# NixieDriver.net
KiCad netlist of a schematic drawn in Altium Designer
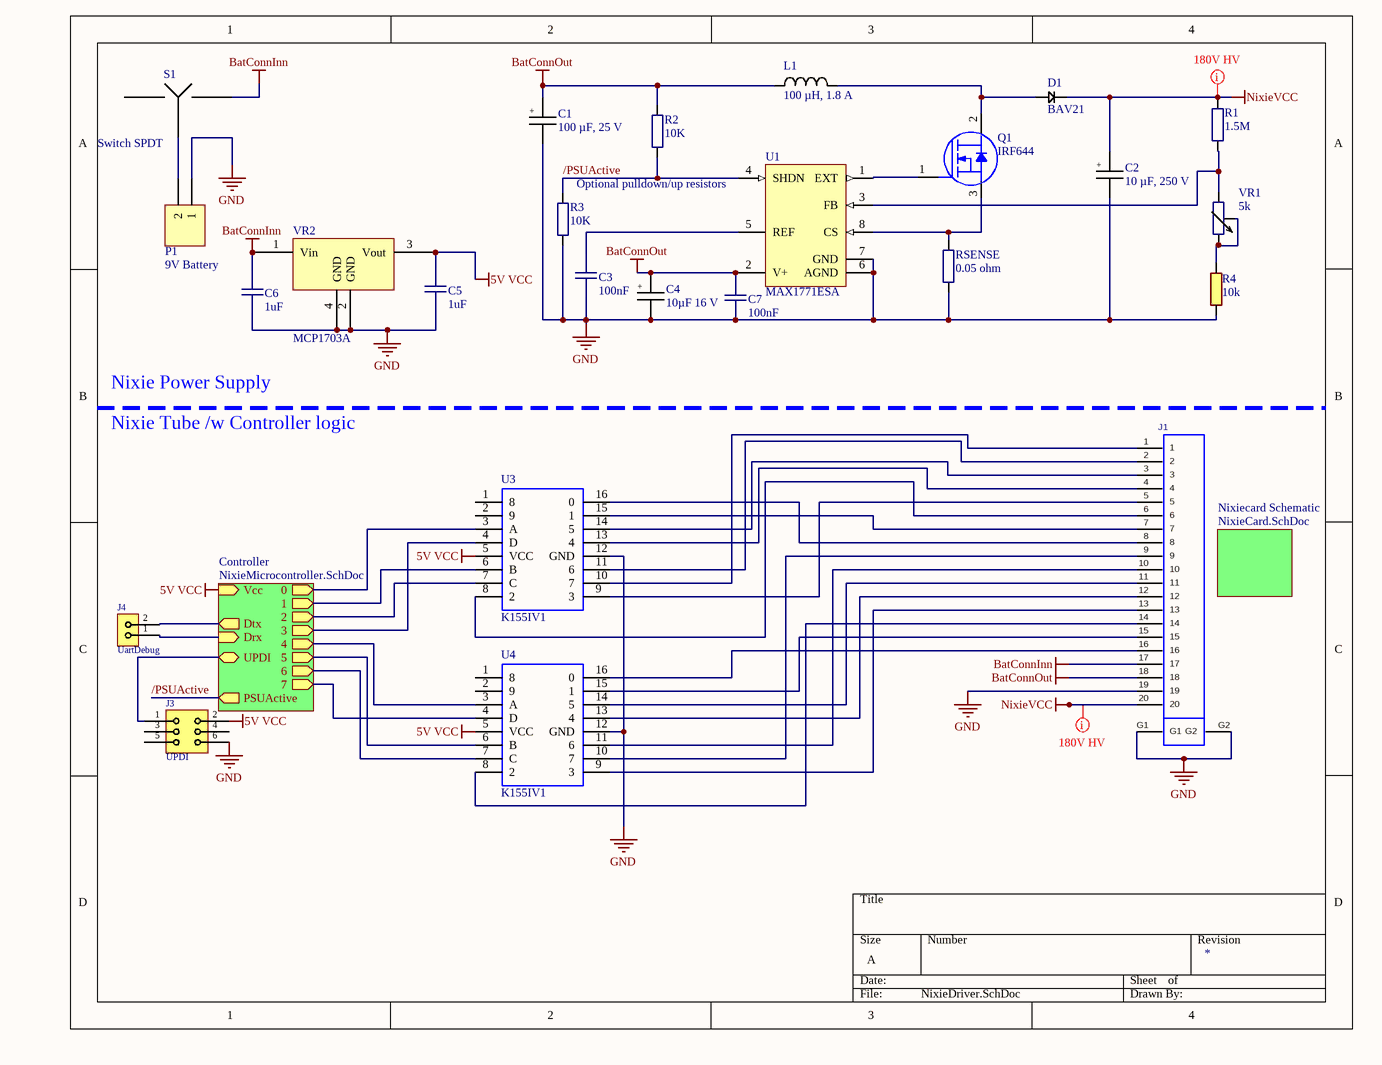
[diagram p0: NixieDriver.SchDoc, right]

(export (version "E")
  (design (tool "Eeschema 10.0.6"))
  (components
    (comp (ref "C1")
      (value "100 µF, 25 V")
      (footprint "CAPAE9583X65M")
      (libsource (lib "Schlib1") (part "EEEFK1E101P"))
    )
    (comp (ref "C2")
      (value "10 µF, 250 V")
      (footprint "CAPAE112103X170M")
      (libsource (lib "Schlib1") (part "EEVEB2E100Q"))
    )
    (comp (ref "C3")
      (value "100nF")
      (footprint "CAPC0805(2012)100_N")
      (description "X7R 50V")
      (libsource (lib "OVLib_64") (part "CAP"))
    )
    (comp (ref "C4")
      (value "10µF 16 V")
      (footprint "CAPAE5542X55M")
      (libsource (lib "Schlib1") (part "EEEFC1C100R"))
    )
    (comp (ref "C5")
      (value "1uF")
      (footprint "CAPC0805(2012)100_N")
      (description "X7R 50V 10%")
      (libsource (lib "OVLib_64") (part "CAP"))
    )
    (comp (ref "C6")
      (value "1uF")
      (footprint "CAPC0805(2012)100_N")
      (description "X7R 50V 10%")
      (libsource (lib "OVLib_64") (part "CAP"))
    )
    (comp (ref "C7")
      (value "100nF")
      (footprint "CAPC0805(2012)100_N")
      (description "X7R 50V")
      (libsource (lib "OVLib_64") (part "CAP"))
    )
    (comp (ref "D1") (value "BAV21") (footprint "DO-41") (libsource (lib "OVLib_64") (part "Diode")))
    (comp (ref "J1")
      (value "ZF1-20-01-XX-WT")
      (footprint "ZF1-20-01-XX-WT")
      (description "ZERO INSERTION FORCE 1mm ASSEMBLY, BOTTOM CONTACT.")
      (libsource (lib "ZF1-20-01-XX-WT") (part "ZF1-20-01-XX-WT"))
    )
    (comp (ref "J3")
      (value "UPDI")
      (footprint "HDRV6W64P254_2X3_762X508X900B")
      (libsource (lib "OVLib_64") (part "Header2x3"))
    )
    (comp (ref "J4")
      (value "UartDebug")
      (footprint "HDRV2W64P254_1X2_508X254X900B")
      (libsource (lib "OVLib_64") (part "Header1x2"))
    )
    (comp (ref "L1")
      (value "100 µH, 1.8 A")
      (footprint "B82479A1")
      (libsource (lib "Schlib1") (part "B82479A1104M"))
    )
    (comp (ref "P1")
      (value "9V Battery")
      (footprint "HDR1X2")
      (description "Header, 2-Pin")
      (fields (field (name "PUBLISHER") "Altium Limited"))
      (libsource (lib "Miscellaneous Connectors") (part "Header 2"))
    )
    (comp (ref "Q1")
      (value "IRF644")
      (footprint "TO-220-3P")
      (description "Power MOSFET")
      (libsource (lib "OVLib_64") (part "MOSFET_N_GDS"))
    )
    (comp (ref "R1") (value "1.5M") (footprint "RC2512") (libsource (lib "Schlib1") (part "Resistor")))
    (comp (ref "R2") (value "10K") (footprint "R0805") (libsource (lib "Schlib1") (part "Resistor")))
    (comp (ref "R3") (value "10K") (footprint "R0805") (libsource (lib "Schlib1") (part "Resistor")))
    (comp (ref "R4")
      (value "10k")
      (footprint "RESC0805(2012)_N")
      (description "0.1W 1% Thick film resistor")
      (libsource (lib "OVLib_64") (part "Resistor2"))
    )
    (comp (ref "RSENSE")
      (value "0.05 ohm")
      (footprint "LR2010")
      (libsource (lib "Schlib1") (part "Resistor"))
    )
    (comp (ref "S1") (value "Switch SPDT") (footprint "3TH") (libsource (lib "Schlib1") (part "Switch SPDT")))
    (comp (ref "U1")
      (value "MAX1771ESA")
      (footprint "S8-5_L")
      (fields (field (name "MANUFACTURER") "Maxim"))
      (libsource (lib "Altium Content Vault") (part "MAXM-MAX1771-8"))
    )
    (comp (ref "U3")
      (value "K155IV1")
      (footprint "CircuitWorks-DIP16")
      (libsource (lib "OVLib_64") (part "SN74141"))
    )
    (comp (ref "U4")
      (value "K155IV1")
      (footprint "CircuitWorks-DIP16")
      (libsource (lib "OVLib_64") (part "SN74141"))
    )
    (comp (ref "VR1")
      (value "5k")
      (footprint "PVG3A trimpot")
      (libsource (lib "Schlib1") (part "PVG3A502C01R00"))
    )
    (comp (ref "VR2")
      (value "MCP1703A")
      (footprint "SOT230P700X180-4N")
      (libsource (lib "Schlib1") (part "MCP1703A"))
    )
  )
  (nets
    (net (code "1") (name "/0") (class "Default")
      (node (ref "U3") (pin "3") (pinfunction "A_3") (pintype "passive"))
    )
    (net (code "2") (name "/1") (class "Default")
      (node (ref "U3") (pin "6") (pinfunction "B_6") (pintype "passive"))
    )
    (net (code "3") (name "/2") (class "Default")
      (node (ref "U3") (pin "7") (pinfunction "C_7") (pintype "passive"))
    )
    (net (code "4") (name "/3") (class "Default")
      (node (ref "U3") (pin "4") (pinfunction "D_4") (pintype "passive"))
    )
    (net (code "5") (name "/4") (class "Default")
      (node (ref "U4") (pin "3") (pinfunction "A_3") (pintype "passive"))
    )
    (net (code "6") (name "/5") (class "Default")
      (node (ref "U4") (pin "6") (pinfunction "B_6") (pintype "passive"))
    )
    (net (code "7") (name "/6") (class "Default")
      (node (ref "U4") (pin "7") (pinfunction "C_7") (pintype "passive"))
    )
    (net (code "8") (name "/7") (class "Default")
      (node (ref "U4") (pin "4") (pinfunction "D_4") (pintype "passive"))
    )
    (net (code "9") (name "/Drx") (class "Default")
      (node (ref "J4") (pin "1") (pinfunction "1_1") (pintype "passive"))
    )
    (net (code "10") (name "/Dtx") (class "Default")
      (node (ref "J4") (pin "2") (pinfunction "2_2") (pintype "passive"))
    )
    (net (code "11") (name "/UPDI") (class "Default")
      (node (ref "J3") (pin "1") (pinfunction "UDPI_1") (pintype "passive"))
    )
    (net (code "12") (name "/{slash}PSUActive") (class "Default")
      (node (ref "R2") (pin "1") (pinfunction "1_1") (pintype "passive"))
      (node (ref "R3") (pin "2") (pinfunction "2_2") (pintype "passive"))
      (node (ref "U1") (pin "4") (pinfunction "SHDN_4") (pintype "input"))
    )
    (net (code "13") (name "5V VCC") (class "Default")
      (node (ref "C5") (pin "2") (pinfunction "2_2") (pintype "passive"))
      (node (ref "J3") (pin "2") (pinfunction "VCC_2") (pintype "passive"))
      (node (ref "U3") (pin "5") (pinfunction "VCC_5") (pintype "power_in"))
      (node (ref "U4") (pin "5") (pinfunction "VCC_5") (pintype "power_in"))
      (node (ref "VR2") (pin "3") (pinfunction "Vout_3") (pintype "passive"))
    )
    (net (code "14") (name "BatConnInn") (class "Default")
      (node (ref "C6") (pin "2") (pinfunction "2_2") (pintype "passive"))
      (node (ref "J1") (pin "17") (pinfunction "17_17") (pintype "passive"))
      (node (ref "S1") (pin "3") (pinfunction "K_3") (pintype "passive"))
      (node (ref "VR2") (pin "1") (pinfunction "Vin_1") (pintype "passive"))
    )
    (net (code "15") (name "BatConnOut") (class "Default")
      (node (ref "C1") (pin "1") (pinfunction "1_1") (pintype "passive"))
      (node (ref "C4") (pin "1") (pinfunction "1_1") (pintype "passive"))
      (node (ref "C7") (pin "1") (pinfunction "1_1") (pintype "passive"))
      (node (ref "J1") (pin "18") (pinfunction "18_18") (pintype "passive"))
      (node (ref "L1") (pin "1") (pinfunction "1_1") (pintype "passive"))
      (node (ref "R2") (pin "2") (pinfunction "2_2") (pintype "passive"))
      (node (ref "U1") (pin "2") (pinfunction "V+_2") (pintype "power_in"))
    )
    (net (code "16") (name "GND") (class "Default")
      (node (ref "C1") (pin "2") (pinfunction "2_2") (pintype "passive"))
      (node (ref "C2") (pin "2") (pinfunction "2_2") (pintype "passive"))
      (node (ref "C3") (pin "1") (pinfunction "1_1") (pintype "passive"))
      (node (ref "C4") (pin "2") (pinfunction "2_2") (pintype "passive"))
      (node (ref "C5") (pin "1") (pinfunction "1_1") (pintype "passive"))
      (node (ref "C6") (pin "1") (pinfunction "1_1") (pintype "passive"))
      (node (ref "C7") (pin "2") (pinfunction "2_2") (pintype "passive"))
      (node (ref "J1") (pin "19") (pinfunction "19_19") (pintype "passive"))
      (node (ref "J1") (pin "G1") (pinfunction "G1_G1") (pintype "passive"))
      (node (ref "J1") (pin "G2") (pinfunction "G2_G2") (pintype "passive"))
      (node (ref "J3") (pin "6") (pinfunction "GND_6") (pintype "passive"))
      (node (ref "P1") (pin "1") (pinfunction "1_1") (pintype "passive"))
      (node (ref "R3") (pin "1") (pinfunction "1_1") (pintype "passive"))
      (node (ref "R4") (pin "1") (pinfunction "1_1") (pintype "passive"))
      (node (ref "RSENSE") (pin "1") (pinfunction "1_1") (pintype "passive"))
      (node (ref "U1") (pin "6") (pinfunction "AGND_6") (pintype "power_in"))
      (node (ref "U1") (pin "7") (pinfunction "GND_7") (pintype "power_in"))
      (node (ref "U3") (pin "12") (pinfunction "GND_12") (pintype "passive"))
      (node (ref "U4") (pin "12") (pinfunction "GND_12") (pintype "passive"))
      (node (ref "VR2") (pin "2") (pinfunction "GND_2") (pintype "passive"))
      (node (ref "VR2") (pin "4") (pinfunction "GND_4") (pintype "passive"))
    )
    (net (code "17") (name "Net-(D1-A)") (class "Default")
      (node (ref "D1") (pin "1") (pinfunction "A_1") (pintype "passive"))
      (node (ref "L1") (pin "2") (pinfunction "2_2") (pintype "passive"))
      (node (ref "Q1") (pin "2") (pinfunction "Source_2") (pintype "passive"))
    )
    (net (code "18") (name "Net-(P1-Pad2)") (class "Default")
      (node (ref "P1") (pin "2") (pinfunction "2_2") (pintype "passive"))
      (node (ref "S1") (pin "2") (pinfunction "K_2") (pintype "passive"))
    )
    (net (code "19") (name "Net-(Q1-Drain)") (class "Default")
      (node (ref "Q1") (pin "3") (pinfunction "Drain_3") (pintype "passive"))
      (node (ref "RSENSE") (pin "2") (pinfunction "2_2") (pintype "passive"))
      (node (ref "U1") (pin "8") (pinfunction "CS_8") (pintype "input"))
    )
    (net (code "20") (name "Net-(Q1-Gate)") (class "Default")
      (node (ref "Q1") (pin "1") (pinfunction "Gate_1") (pintype "passive"))
      (node (ref "U1") (pin "1") (pinfunction "EXT_1") (pintype "output"))
    )
    (net (code "21") (name "Net-(R4-Pad2)") (class "Default")
      (node (ref "R4") (pin "2") (pinfunction "2_2") (pintype "passive"))
      (node (ref "VR1") (pin "1") (pinfunction "1_1") (pintype "passive"))
      (node (ref "VR1") (pin "2") (pinfunction "2_2") (pintype "passive"))
    )
    (net (code "22") (name "Net-(U1-FB)") (class "Default")
      (node (ref "R1") (pin "1") (pinfunction "1_1") (pintype "passive"))
      (node (ref "U1") (pin "3") (pinfunction "FB_3") (pintype "input"))
      (node (ref "VR1") (pin "3") (pinfunction "3_3") (pintype "passive"))
    )
    (net (code "23") (name "Net-(U1-REF)") (class "Default")
      (node (ref "C3") (pin "2") (pinfunction "2_2") (pintype "passive"))
      (node (ref "U1") (pin "5") (pinfunction "REF_5") (pintype "passive"))
    )
    (net (code "24") (name "Net-(U3-0)") (class "Default")
      (node (ref "J1") (pin "8") (pinfunction "8_8") (pintype "passive"))
      (node (ref "U3") (pin "16") (pinfunction "0_16") (pintype "passive"))
    )
    (net (code "25") (name "Net-(U3-1)") (class "Default")
      (node (ref "J1") (pin "7") (pinfunction "7_7") (pintype "passive"))
      (node (ref "U3") (pin "15") (pinfunction "1_15") (pintype "passive"))
    )
    (net (code "26") (name "Net-(U3-2)") (class "Default")
      (node (ref "J1") (pin "6") (pinfunction "6_6") (pintype "passive"))
      (node (ref "U3") (pin "8") (pinfunction "2_8") (pintype "passive"))
    )
    (net (code "27") (name "Net-(U3-3)") (class "Default")
      (node (ref "J1") (pin "5") (pinfunction "5_5") (pintype "passive"))
      (node (ref "U3") (pin "9") (pinfunction "3_9") (pintype "passive"))
    )
    (net (code "28") (name "Net-(U3-4)") (class "Default")
      (node (ref "J1") (pin "4") (pinfunction "4_4") (pintype "passive"))
      (node (ref "U3") (pin "13") (pinfunction "4_13") (pintype "passive"))
    )
    (net (code "29") (name "Net-(U3-5)") (class "Default")
      (node (ref "J1") (pin "3") (pinfunction "3_3") (pintype "passive"))
      (node (ref "U3") (pin "14") (pinfunction "5_14") (pintype "passive"))
    )
    (net (code "30") (name "Net-(U3-6)") (class "Default")
      (node (ref "J1") (pin "2") (pinfunction "2_2") (pintype "passive"))
      (node (ref "U3") (pin "11") (pinfunction "6_11") (pintype "passive"))
    )
    (net (code "31") (name "Net-(U3-7)") (class "Default")
      (node (ref "J1") (pin "1") (pinfunction "1_1") (pintype "passive"))
      (node (ref "U3") (pin "10") (pinfunction "7_10") (pintype "passive"))
    )
    (net (code "32") (name "Net-(U4-0)") (class "Default")
      (node (ref "J1") (pin "16") (pinfunction "16_16") (pintype "passive"))
      (node (ref "U4") (pin "16") (pinfunction "0_16") (pintype "passive"))
    )
    (net (code "33") (name "Net-(U4-1)") (class "Default")
      (node (ref "J1") (pin "15") (pinfunction "15_15") (pintype "passive"))
      (node (ref "U4") (pin "15") (pinfunction "1_15") (pintype "passive"))
    )
    (net (code "34") (name "Net-(U4-2)") (class "Default")
      (node (ref "J1") (pin "14") (pinfunction "14_14") (pintype "passive"))
      (node (ref "U4") (pin "8") (pinfunction "2_8") (pintype "passive"))
    )
    (net (code "35") (name "Net-(U4-3)") (class "Default")
      (node (ref "J1") (pin "13") (pinfunction "13_13") (pintype "passive"))
      (node (ref "U4") (pin "9") (pinfunction "3_9") (pintype "passive"))
    )
    (net (code "36") (name "Net-(U4-4)") (class "Default")
      (node (ref "J1") (pin "12") (pinfunction "12_12") (pintype "passive"))
      (node (ref "U4") (pin "13") (pinfunction "4_13") (pintype "passive"))
    )
    (net (code "37") (name "Net-(U4-5)") (class "Default")
      (node (ref "J1") (pin "11") (pinfunction "11_11") (pintype "passive"))
      (node (ref "U4") (pin "14") (pinfunction "5_14") (pintype "passive"))
    )
    (net (code "38") (name "Net-(U4-6)") (class "Default")
      (node (ref "J1") (pin "10") (pinfunction "10_10") (pintype "passive"))
      (node (ref "U4") (pin "11") (pinfunction "6_11") (pintype "passive"))
    )
    (net (code "39") (name "Net-(U4-7)") (class "Default")
      (node (ref "J1") (pin "9") (pinfunction "9_9") (pintype "passive"))
      (node (ref "U4") (pin "10") (pinfunction "7_10") (pintype "passive"))
    )
    (net (code "40") (name "NixieVCC") (class "Default")
      (node (ref "C2") (pin "1") (pinfunction "1_1") (pintype "passive"))
      (node (ref "D1") (pin "2") (pinfunction "K_2") (pintype "passive"))
      (node (ref "J1") (pin "20") (pinfunction "20_20") (pintype "passive"))
      (node (ref "R1") (pin "2") (pinfunction "2_2") (pintype "passive"))
    )
    (net (code "41") (name "unconnected-(J3-Pad3)") (class "Default")
      (node (ref "J3") (pin "3") (pinfunction "3_3") (pintype "passive"))
    )
    (net (code "42") (name "unconnected-(J3-Pad4)") (class "Default")
      (node (ref "J3") (pin "4") (pinfunction "4_4") (pintype "passive"))
    )
    (net (code "43") (name "unconnected-(J3-Pad5)") (class "Default")
      (node (ref "J3") (pin "5") (pinfunction "5_5") (pintype "passive"))
    )
    (net (code "44") (name "unconnected-(S1-K-Pad1)") (class "Default")
      (node (ref "S1") (pin "1") (pinfunction "K_1") (pintype "passive"))
    )
    (net (code "45") (name "unconnected-(U3-8-Pad1)") (class "Default")
      (node (ref "U3") (pin "1") (pinfunction "8_1") (pintype "passive"))
    )
    (net (code "46") (name "unconnected-(U3-9-Pad2)") (class "Default")
      (node (ref "U3") (pin "2") (pinfunction "9_2") (pintype "passive"))
    )
    (net (code "47") (name "unconnected-(U4-8-Pad1)") (class "Default")
      (node (ref "U4") (pin "1") (pinfunction "8_1") (pintype "passive"))
    )
    (net (code "48") (name "unconnected-(U4-9-Pad2)") (class "Default")
      (node (ref "U4") (pin "2") (pinfunction "9_2") (pintype "passive"))
    )
  )
)
